# Peripherals.net
KiCad netlist of a schematic drawn in Altium Designer
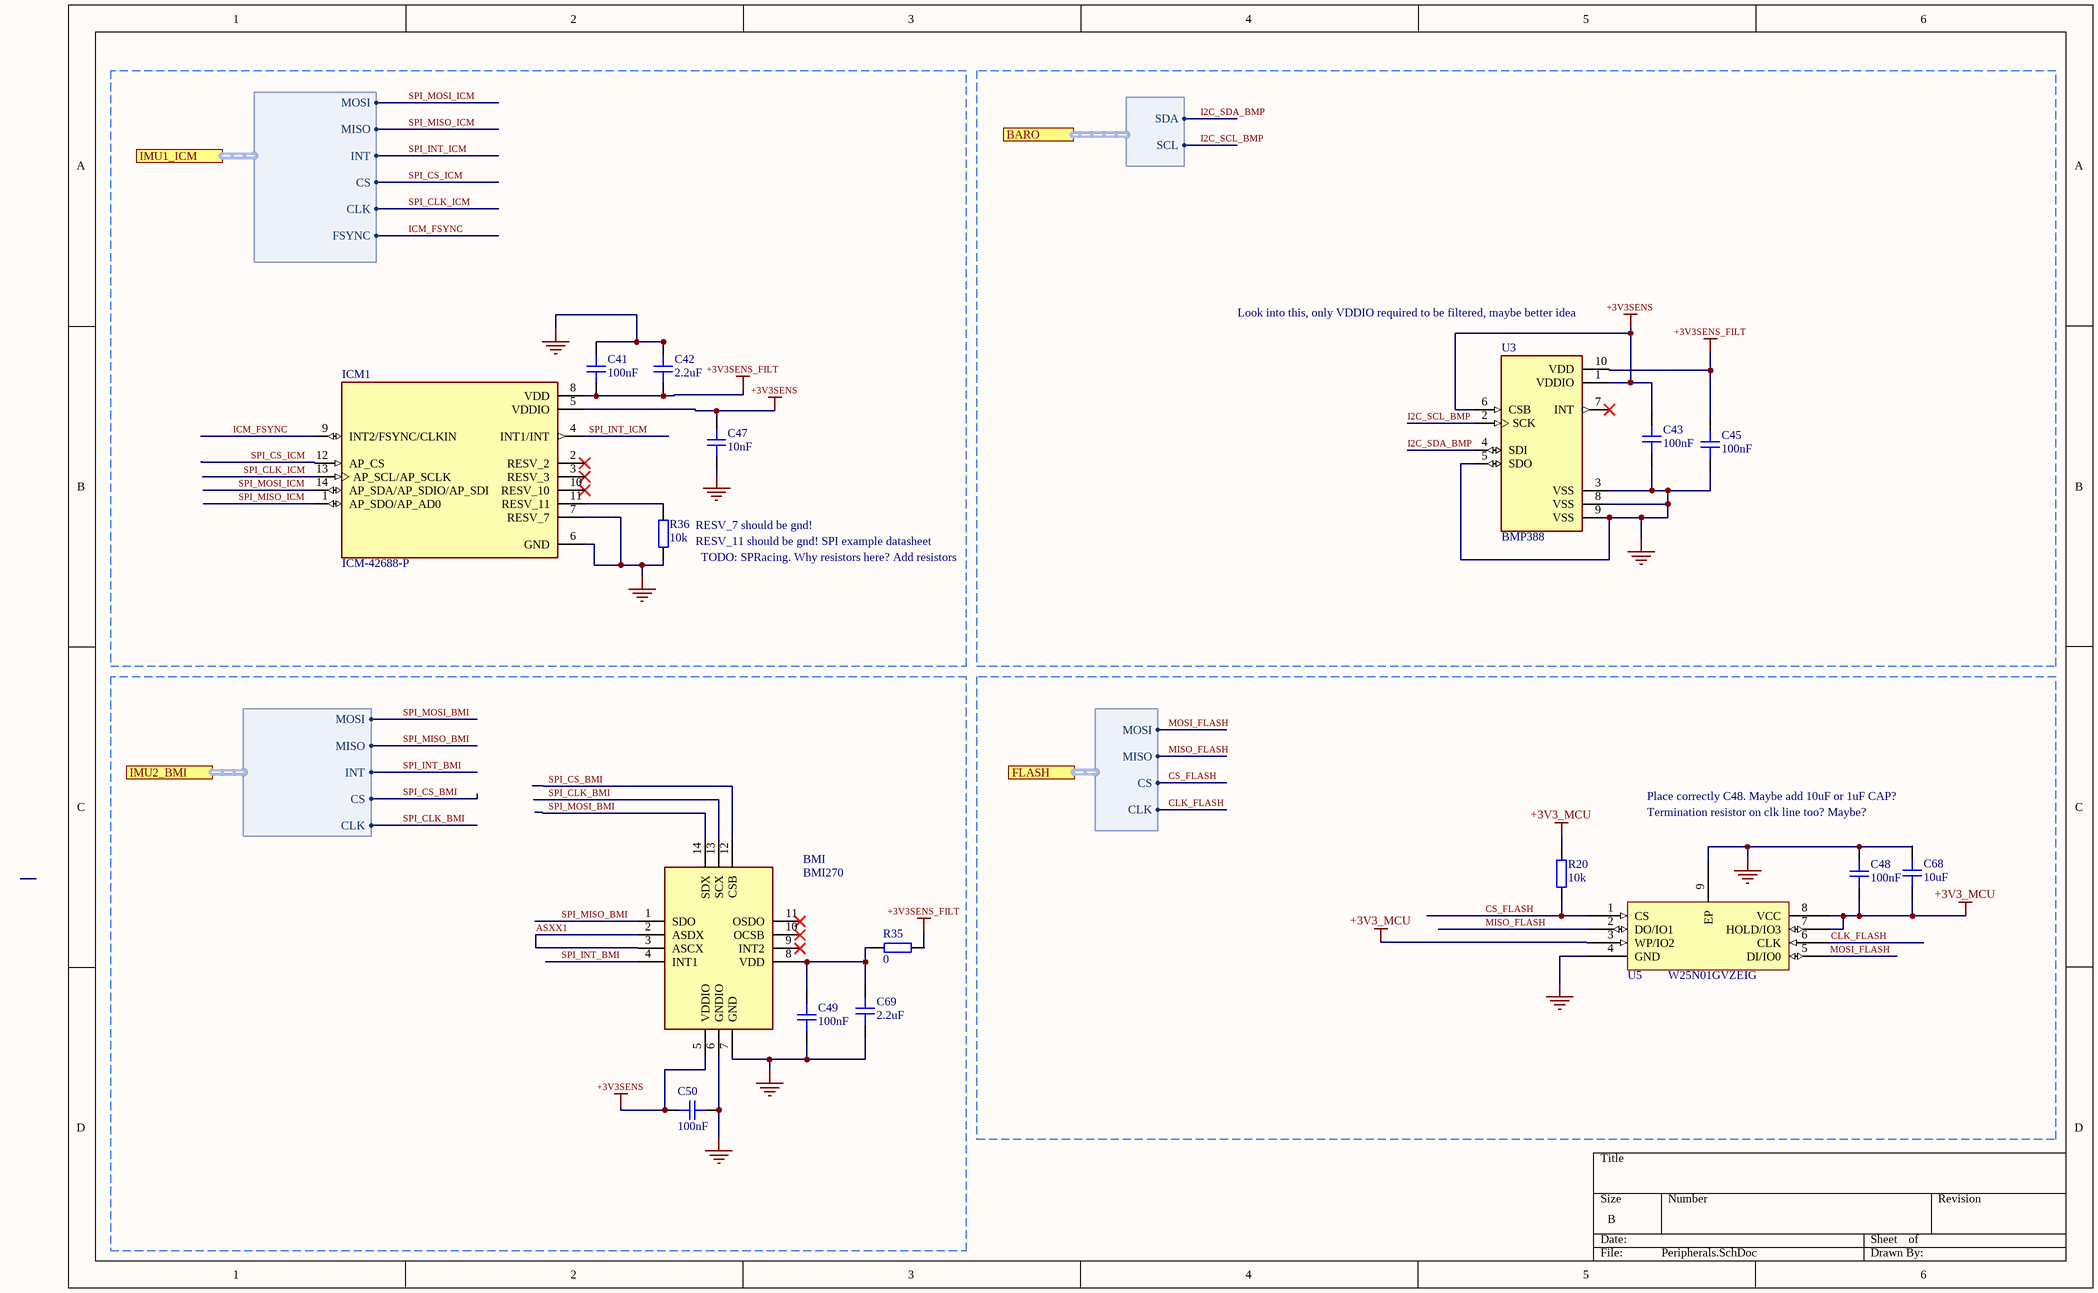
[diagram p0: Peripherals.SchDoc]

(export (version "E")
  (design (tool "Eeschema 10.0.6"))
  (components
    (comp (ref "BMI")
      (value "BMI270")
      (footprint "Footprint-Lib-Singu:BMI270")
      (description "Integrated Circuit")
      (fields (field (name "MOUSER PART NUMBER") "262-BMI270"))
      (libsource (lib "Schematic-Lib-Singu") (part "BMI270"))
    )
    (comp (ref "C41")
      (value "100nF")
      (footprint "CAP_0201")
      (description "Capacitor SMD 0201")
      (libsource (lib "Schematic-Lib-PhilsLab") (part "CAP_0201"))
    )
    (comp (ref "C42")
      (value "2.2uF")
      (footprint "CAP_0402")
      (description "Capacitor SMD 0402")
      (libsource (lib "Schematic-Lib-PhilsLab") (part "CAP_0402"))
    )
    (comp (ref "C43")
      (value "100nF")
      (footprint "CAP_0201")
      (description "Capacitor SMD 0201")
      (libsource (lib "Schematic-Lib-PhilsLab") (part "CAP_0201"))
    )
    (comp (ref "C45")
      (value "100nF")
      (footprint "CAP_0201")
      (description "Capacitor SMD 0201")
      (libsource (lib "Schematic-Lib-PhilsLab") (part "CAP_0201"))
    )
    (comp (ref "C47")
      (value "10nF")
      (footprint "CAP_0201")
      (description "Capacitor SMD 0201")
      (libsource (lib "Schematic-Lib-PhilsLab") (part "CAP_0201"))
    )
    (comp (ref "C48")
      (value "100nF")
      (footprint "CAP_0201")
      (description "Capacitor SMD 0201")
      (libsource (lib "Schematic-Lib-PhilsLab") (part "CAP_0201"))
    )
    (comp (ref "C49")
      (value "100nF")
      (footprint "CAP_0201")
      (description "Capacitor SMD 0201")
      (libsource (lib "Schematic-Lib-PhilsLab") (part "CAP_0201"))
    )
    (comp (ref "C50")
      (value "100nF")
      (footprint "CAP_0201")
      (description "Capacitor SMD 0201")
      (libsource (lib "Schematic-Lib-PhilsLab") (part "CAP_0201"))
    )
    (comp (ref "C68")
      (value "10uF")
      (footprint "CAP_0402")
      (description "Capacitor SMD 0402")
      (libsource (lib "Schematic-Lib-PhilsLab") (part "CAP_0402"))
    )
    (comp (ref "C69")
      (value "2.2uF")
      (footprint "CAP_0402")
      (description "Capacitor SMD 0402")
      (libsource (lib "Schematic-Lib-PhilsLab") (part "CAP_0402"))
    )
    (comp (ref "ICM1")
      (value "ICM-42688-P")
      (footprint "ICM-42688-P")
      (libsource (lib "Schematic-Lib-Singu") (part "ICM-42688-P"))
    )
    (comp (ref "R20")
      (value "10k")
      (footprint "RES_0201")
      (description "Resistor SMD 0201")
      (libsource (lib "Schematic-Lib-PhilsLab") (part "RES_0201"))
    )
    (comp (ref "R35")
      (value "0")
      (footprint "RES_0402")
      (description "Resistor SMD 0402")
      (libsource (lib "Schematic-Lib-PhilsLab") (part "RES_0402"))
    )
    (comp (ref "R36")
      (value "10k")
      (footprint "RES_0201")
      (description "Resistor SMD 0201")
      (libsource (lib "Schematic-Lib-PhilsLab") (part "RES_0201"))
    )
    (comp (ref "U3")
      (value "BMP388")
      (footprint "PQFN50P200X200X80-10N")
      (description "P-Sensor SPI I2C 1, 25 Bar SMD")
      (libsource (lib "Schematic-Lib-Singu") (part "BMP388"))
    )
    (comp (ref "U5")
      (value "W25N01GVZEIG")
      (footprint "W25N01GVZEIG")
      (fields (field (name "MANUFACTURER") "Windbond Elec") (field (name "LCSC PART") "C88868"))
      (libsource (lib "Schematic-Lib-Singu") (part "W25N01GVZEIG"))
    )
  )
  (nets
    (net (code "5") (name "+3V3SENS") (class "Default")
      (node (ref "BMI") (pin "5") (pinfunction "VDDIO_5") (pintype "passive"))
      (node (ref "C43") (pin "2") (pinfunction "2_2") (pintype "passive"))
      (node (ref "C47") (pin "2") (pinfunction "2_2") (pintype "passive"))
      (node (ref "C50") (pin "2") (pinfunction "2_2") (pintype "passive"))
      (node (ref "ICM1") (pin "5") (pinfunction "VDDIO_5") (pintype "power_in"))
      (node (ref "U3") (pin "1") (pinfunction "VDDIO_1") (pintype "power_in"))
      (node (ref "U3") (pin "6") (pinfunction "CSB_6") (pintype "input"))
    )
    (net (code "6") (name "+3V3SENS_FILT") (class "Default")
      (node (ref "C41") (pin "1") (pinfunction "1_1") (pintype "passive"))
      (node (ref "C42") (pin "1") (pinfunction "1_1") (pintype "passive"))
      (node (ref "C45") (pin "2") (pinfunction "2_2") (pintype "passive"))
      (node (ref "ICM1") (pin "8") (pinfunction "VDD_8") (pintype "power_in"))
      (node (ref "R35") (pin "2") (pinfunction "2_2") (pintype "passive"))
      (node (ref "U3") (pin "10") (pinfunction "VDD_10") (pintype "power_in"))
    )
    (net (code "7") (name "+3V3_MCU") (class "Default")
      (node (ref "C48") (pin "1") (pinfunction "1_1") (pintype "passive"))
      (node (ref "C68") (pin "1") (pinfunction "1_1") (pintype "passive"))
      (node (ref "R20") (pin "2") (pinfunction "2_2") (pintype "passive"))
      (node (ref "U5") (pin "3") (pinfunction "WP/IO2_3") (pintype "input"))
      (node (ref "U5") (pin "7") (pinfunction "HOLD/IO3_7") (pintype "bidirectional"))
      (node (ref "U5") (pin "8") (pinfunction "VCC_8") (pintype "power_in"))
    )
    (net (code "8") (name "/ASXX1") (class "Default")
      (node (ref "BMI") (pin "2") (pinfunction "ASDX_2") (pintype "passive"))
      (node (ref "BMI") (pin "3") (pinfunction "ASCX_3") (pintype "passive"))
    )
    (net (code "9") (name "/CLK_FLASH") (class "Default")
      (node (ref "U5") (pin "6") (pinfunction "CLK_6") (pintype "input"))
    )
    (net (code "10") (name "/CS_FLASH") (class "Default")
      (node (ref "R20") (pin "1") (pinfunction "1_1") (pintype "passive"))
      (node (ref "U5") (pin "1") (pinfunction "CS_1") (pintype "input"))
    )
    (net (code "11") (name "/I2C_SCL_BMP") (class "Default")
      (node (ref "U3") (pin "2") (pinfunction "SCK_2") (pintype "input"))
    )
    (net (code "12") (name "/I2C_SDA_BMP") (class "Default")
      (node (ref "U3") (pin "4") (pinfunction "SDI_4") (pintype "bidirectional"))
    )
    (net (code "13") (name "/ICM_FSYNC") (class "Default")
      (node (ref "ICM1") (pin "9") (pinfunction "INT2/FSYNC/CLKIN_9") (pintype "bidirectional"))
    )
    (net (code "14") (name "/MISO_FLASH") (class "Default")
      (node (ref "U5") (pin "2") (pinfunction "DO/IO1_2") (pintype "bidirectional"))
    )
    (net (code "15") (name "/MOSI_FLASH") (class "Default")
      (node (ref "U5") (pin "5") (pinfunction "DI/IO0_5") (pintype "bidirectional"))
    )
    (net (code "16") (name "/SPI_CLK_BMI") (class "Default")
      (node (ref "BMI") (pin "13") (pinfunction "SCX_13") (pintype "passive"))
    )
    (net (code "17") (name "/SPI_CLK_ICM") (class "Default")
      (node (ref "ICM1") (pin "13") (pinfunction "AP_SCL/AP_SCLK_13") (pintype "input"))
    )
    (net (code "18") (name "/SPI_CS_BMI") (class "Default")
      (node (ref "BMI") (pin "12") (pinfunction "CSB_12") (pintype "passive"))
    )
    (net (code "19") (name "/SPI_CS_ICM") (class "Default")
      (node (ref "ICM1") (pin "12") (pinfunction "AP_CS_12") (pintype "input"))
    )
    (net (code "20") (name "/SPI_INT_BMI") (class "Default")
      (node (ref "BMI") (pin "4") (pinfunction "INT1_4") (pintype "passive"))
    )
    (net (code "21") (name "/SPI_INT_ICM") (class "Default")
      (node (ref "ICM1") (pin "4") (pinfunction "INT1/INT_4") (pintype "output"))
    )
    (net (code "22") (name "/SPI_MISO_BMI") (class "Default")
      (node (ref "BMI") (pin "1") (pinfunction "SDO_1") (pintype "passive"))
    )
    (net (code "23") (name "/SPI_MISO_ICM") (class "Default")
      (node (ref "ICM1") (pin "1") (pinfunction "AP_SDO/AP_AD0_1") (pintype "bidirectional"))
    )
    (net (code "24") (name "/SPI_MOSI_BMI") (class "Default")
      (node (ref "BMI") (pin "14") (pinfunction "SDX_14") (pintype "passive"))
    )
    (net (code "25") (name "/SPI_MOSI_ICM") (class "Default")
      (node (ref "ICM1") (pin "14") (pinfunction "AP_SDA/AP_SDIO/AP_SDI_14") (pintype "bidirectional"))
    )
    (net (code "30") (name "GND") (class "Default")
      (node (ref "BMI") (pin "6") (pinfunction "GNDIO_6") (pintype "passive"))
      (node (ref "BMI") (pin "7") (pinfunction "GND_7") (pintype "passive"))
      (node (ref "C41") (pin "2") (pinfunction "2_2") (pintype "passive"))
      (node (ref "C42") (pin "2") (pinfunction "2_2") (pintype "passive"))
      (node (ref "C43") (pin "1") (pinfunction "1_1") (pintype "passive"))
      (node (ref "C45") (pin "1") (pinfunction "1_1") (pintype "passive"))
      (node (ref "C47") (pin "1") (pinfunction "1_1") (pintype "passive"))
      (node (ref "C48") (pin "2") (pinfunction "2_2") (pintype "passive"))
      (node (ref "C49") (pin "1") (pinfunction "1_1") (pintype "passive"))
      (node (ref "C50") (pin "1") (pinfunction "1_1") (pintype "passive"))
      (node (ref "C68") (pin "2") (pinfunction "2_2") (pintype "passive"))
      (node (ref "C69") (pin "1") (pinfunction "1_1") (pintype "passive"))
      (node (ref "ICM1") (pin "6") (pinfunction "GND_6") (pintype "power_in"))
      (node (ref "ICM1") (pin "7") (pinfunction "RESV_7_7") (pintype "passive"))
      (node (ref "R36") (pin "1") (pinfunction "1_1") (pintype "passive"))
      (node (ref "U3") (pin "3") (pinfunction "VSS_3") (pintype "power_in"))
      (node (ref "U3") (pin "5") (pinfunction "SDO_5") (pintype "bidirectional"))
      (node (ref "U3") (pin "8") (pinfunction "VSS_8") (pintype "power_in"))
      (node (ref "U3") (pin "9") (pinfunction "VSS_9") (pintype "power_in"))
      (node (ref "U5") (pin "4") (pinfunction "GND_4") (pintype "passive"))
      (node (ref "U5") (pin "9") (pinfunction "EP_9") (pintype "passive"))
    )
    (net (code "31") (name "Net-(BMI-VDD)") (class "Default")
      (node (ref "BMI") (pin "8") (pinfunction "VDD_8") (pintype "passive"))
      (node (ref "C49") (pin "2") (pinfunction "2_2") (pintype "passive"))
      (node (ref "C69") (pin "2") (pinfunction "2_2") (pintype "passive"))
      (node (ref "R35") (pin "1") (pinfunction "1_1") (pintype "passive"))
    )
    (net (code "32") (name "Net-(ICM1-RESV_11)") (class "Default")
      (node (ref "ICM1") (pin "11") (pinfunction "RESV_11_11") (pintype "passive"))
      (node (ref "R36") (pin "2") (pinfunction "2_2") (pintype "passive"))
    )
    (net (code "33") (name "unconnected-(BMI-INT2-Pad9)") (class "Default")
      (node (ref "BMI") (pin "9") (pinfunction "INT2_9") (pintype "passive+no_connect"))
    )
    (net (code "34") (name "unconnected-(BMI-OCSB-Pad10)") (class "Default")
      (node (ref "BMI") (pin "10") (pinfunction "OCSB_10") (pintype "passive+no_connect"))
    )
    (net (code "35") (name "unconnected-(BMI-OSDO-Pad11)") (class "Default")
      (node (ref "BMI") (pin "11") (pinfunction "OSDO_11") (pintype "passive+no_connect"))
    )
    (net (code "36") (name "unconnected-(ICM1-RESV_2-Pad2)") (class "Default")
      (node (ref "ICM1") (pin "2") (pinfunction "RESV_2_2") (pintype "passive+no_connect"))
    )
    (net (code "37") (name "unconnected-(ICM1-RESV_3-Pad3)") (class "Default")
      (node (ref "ICM1") (pin "3") (pinfunction "RESV_3_3") (pintype "passive+no_connect"))
    )
    (net (code "38") (name "unconnected-(ICM1-RESV_10-Pad10)") (class "Default")
      (node (ref "ICM1") (pin "10") (pinfunction "RESV_10_10") (pintype "passive+no_connect"))
    )
    (net (code "39") (name "unconnected-(U3-INT-Pad7)") (class "Default")
      (node (ref "U3") (pin "7") (pinfunction "INT_7") (pintype "output+no_connect"))
    )
  )
)
